# V1_1_20231208_1.net
KiCad netlist of a schematic drawn in Altium Designer
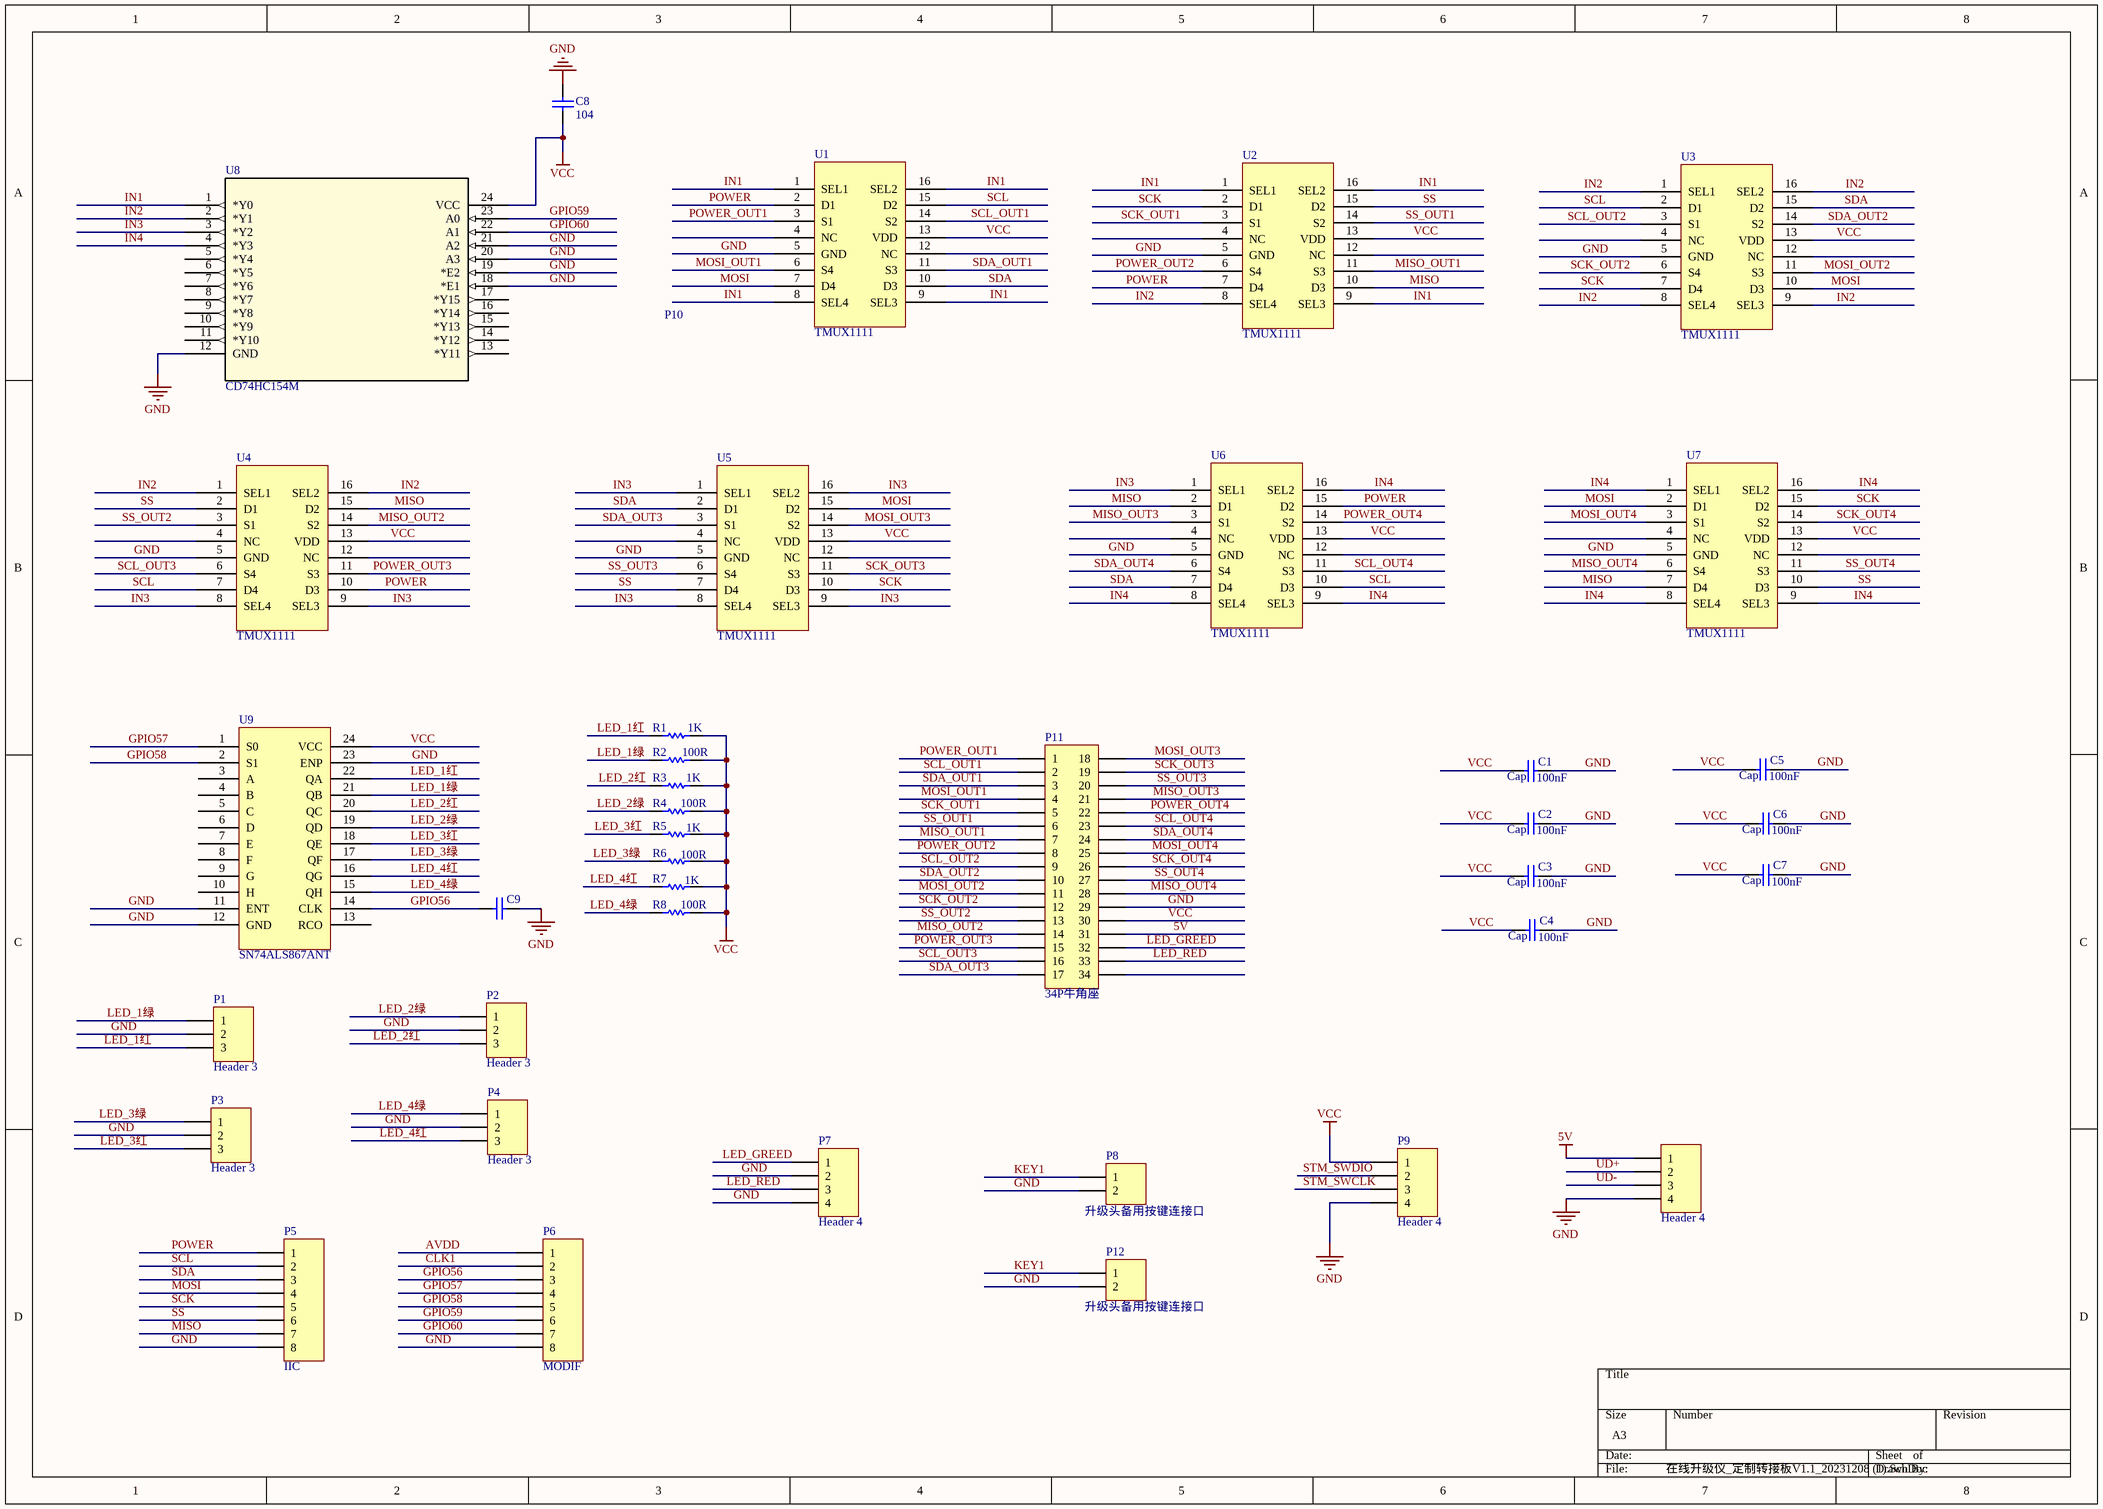
[diagram p0: 在线升级仪_定制转接板V1.1_20231208 (1).SchDoc]

(export (version "E")
  (design (tool "Eeschema 10.0.6"))
  (components
    (comp (ref "C1")
      (value "Cap")
      (footprint "0603")
      (description "Capacitor")
      (fields (field (name "ALTIUM_VALUE") "100nF") (field (name "PUBLISHER") "Altium Limited"))
      (libsource (lib "Miscellaneous Devices") (part "Cap"))
    )
    (comp (ref "C2")
      (value "Cap")
      (footprint "0603")
      (description "Capacitor")
      (fields (field (name "ALTIUM_VALUE") "100nF") (field (name "PUBLISHER") "Altium Limited"))
      (libsource (lib "Miscellaneous Devices") (part "Cap"))
    )
    (comp (ref "C3")
      (value "Cap")
      (footprint "0603")
      (description "Capacitor")
      (fields (field (name "ALTIUM_VALUE") "100nF") (field (name "PUBLISHER") "Altium Limited"))
      (libsource (lib "Miscellaneous Devices") (part "Cap"))
    )
    (comp (ref "C4")
      (value "Cap")
      (footprint "0603")
      (description "Capacitor")
      (fields (field (name "ALTIUM_VALUE") "100nF") (field (name "PUBLISHER") "Altium Limited"))
      (libsource (lib "Miscellaneous Devices") (part "Cap"))
    )
    (comp (ref "C5")
      (value "Cap")
      (footprint "0603")
      (description "Capacitor")
      (fields (field (name "ALTIUM_VALUE") "100nF") (field (name "PUBLISHER") "Altium Limited"))
      (libsource (lib "Miscellaneous Devices") (part "Cap"))
    )
    (comp (ref "C6")
      (value "Cap")
      (footprint "0603")
      (description "Capacitor")
      (fields (field (name "ALTIUM_VALUE") "100nF") (field (name "PUBLISHER") "Altium Limited"))
      (libsource (lib "Miscellaneous Devices") (part "Cap"))
    )
    (comp (ref "C7")
      (value "Cap")
      (footprint "0603")
      (description "Capacitor")
      (fields (field (name "ALTIUM_VALUE") "100nF") (field (name "PUBLISHER") "Altium Limited"))
      (libsource (lib "Miscellaneous Devices") (part "Cap"))
    )
    (comp (ref "C8")
      (value "104")
      (footprint "0603")
      (description "Capacitor (Semiconductor SIM Model)")
      (fields (field (name "Comment") "Cap Semi") (field (name "PUBLISHER") "Altium Limited"))
      (libsource (lib "Miscellaneous Devices") (part "Cap Semi"))
    )
    (comp (ref "C9")
      (value "Cap Semi")
      (footprint "0603")
      (description "Capacitor (Semiconductor SIM Model)")
      (fields (field (name "PUBLISHER") "Altium Limited"))
      (libsource (lib "Miscellaneous Devices") (part "Cap Semi"))
    )
    (comp (ref "P1")
      (value "Header 3")
      (footprint "HDR1X3")
      (description "Header, 3-Pin")
      (fields (field (name "PUBLISHER") "Altium Limited"))
      (libsource (lib "Miscellaneous Connectors") (part "Header 3"))
    )
    (comp (ref "P2")
      (value "Header 3")
      (footprint "HDR1X3")
      (description "Header, 3-Pin")
      (fields (field (name "PUBLISHER") "Altium Limited"))
      (libsource (lib "Miscellaneous Connectors") (part "Header 3"))
    )
    (comp (ref "P3")
      (value "Header 3")
      (footprint "HDR1X3")
      (description "Header, 3-Pin")
      (fields (field (name "PUBLISHER") "Altium Limited"))
      (libsource (lib "Miscellaneous Connectors") (part "Header 3"))
    )
    (comp (ref "P4")
      (value "Header 3")
      (footprint "HDR1X3")
      (description "Header, 3-Pin")
      (fields (field (name "PUBLISHER") "Altium Limited"))
      (libsource (lib "Miscellaneous Connectors") (part "Header 3"))
    )
    (comp (ref "P5")
      (value "IIC")
      (footprint "RJ45网络插座")
      (description "Header, 8-Pin")
      (fields (field (name "PUBLISHER") "Altium Limited"))
      (libsource (lib "Miscellaneous Connectors") (part "Header 8"))
    )
    (comp (ref "P6")
      (value "MODIF")
      (footprint "RJ45网络插座")
      (description "Header, 8-Pin")
      (fields (field (name "PUBLISHER") "Altium Limited"))
      (libsource (lib "Miscellaneous Connectors") (part "Header 8"))
    )
    (comp (ref "P7")
      (value "Header 4")
      (footprint "4pin_1.25mm")
      (description "Header, 4-Pin")
      (fields (field (name "PUBLISHER") "Altium Limited"))
      (libsource (lib "Miscellaneous Connectors") (part "Header 4"))
    )
    (comp (ref "P8")
      (value "升级头备用按键连接口")
      (footprint "2P座子")
      (description "Header, 2-Pin")
      (fields (field (name "PUBLISHER") "Altium Limited"))
      (libsource (lib "Miscellaneous Connectors") (part "Header 2"))
    )
    (comp (ref "P9")
      (value "Header 4")
      (footprint "PcbLib1:4P座子")
      (description "Header, 4-Pin")
      (fields (field (name "PUBLISHER") "Altium Limited"))
      (libsource (lib "Miscellaneous Connectors") (part "Header 4"))
    )
    (comp (ref "P10")
      (value "Header 4")
      (footprint "4P座子")
      (description "Header, 4-Pin")
      (fields (field (name "PUBLISHER") "Altium Limited"))
      (libsource (lib "Miscellaneous Connectors") (part "Header 4"))
    )
    (comp (ref "P11")
      (value "34P牛角座")
      (footprint "34P 牛角座")
      (description "Header, 17-Pin, Dual row")
      (fields (field (name "PUBLISHER") "Altium Limited"))
      (libsource (lib "Miscellaneous Connectors") (part "Header 17X2A"))
    )
    (comp (ref "P12")
      (value "升级头备用按键连接口")
      (footprint "2P座子")
      (description "Header, 2-Pin")
      (fields (field (name "PUBLISHER") "Altium Limited"))
      (libsource (lib "Miscellaneous Connectors") (part "Header 2"))
    )
    (comp (ref "R1")
      (value "1K")
      (footprint "0603")
      (description "Resistor")
      (fields (field (name "Comment") "Res1") (field (name "PUBLISHER") "Altium Limited"))
      (libsource (lib "Miscellaneous Devices") (part "Res1"))
    )
    (comp (ref "R2")
      (value "100R")
      (footprint "0603")
      (description "Resistor")
      (fields (field (name "Comment") "Res1") (field (name "PUBLISHER") "Altium Limited"))
      (libsource (lib "Miscellaneous Devices") (part "Res1"))
    )
    (comp (ref "R3")
      (value "1K")
      (footprint "0603")
      (description "Resistor")
      (fields (field (name "Comment") "Res1") (field (name "PUBLISHER") "Altium Limited"))
      (libsource (lib "Miscellaneous Devices") (part "Res1"))
    )
    (comp (ref "R4")
      (value "100R")
      (footprint "0603")
      (description "Resistor")
      (fields (field (name "Comment") "Res1") (field (name "PUBLISHER") "Altium Limited"))
      (libsource (lib "Miscellaneous Devices") (part "Res1"))
    )
    (comp (ref "R5")
      (value "1K")
      (footprint "0603")
      (description "Resistor")
      (fields (field (name "Comment") "Res1") (field (name "PUBLISHER") "Altium Limited"))
      (libsource (lib "Miscellaneous Devices") (part "Res1"))
    )
    (comp (ref "R6")
      (value "100R")
      (footprint "0603")
      (description "Resistor")
      (fields (field (name "Comment") "Res1") (field (name "PUBLISHER") "Altium Limited"))
      (libsource (lib "Miscellaneous Devices") (part "Res1"))
    )
    (comp (ref "R7")
      (value "1K")
      (footprint "0603")
      (description "Resistor")
      (fields (field (name "Comment") "Res1") (field (name "PUBLISHER") "Altium Limited"))
      (libsource (lib "Miscellaneous Devices") (part "Res1"))
    )
    (comp (ref "R8")
      (value "100R")
      (footprint "0603")
      (description "Resistor")
      (fields (field (name "Comment") "Res1") (field (name "PUBLISHER") "Altium Limited"))
      (libsource (lib "Miscellaneous Devices") (part "Res1"))
    )
    (comp (ref "U1")
      (value "TMUX1111")
      (footprint "TMUX1111")
      (libsource (lib "Schlib1") (part "Component_3"))
    )
    (comp (ref "U2")
      (value "TMUX1111")
      (footprint "TMUX1111")
      (libsource (lib "Schlib1") (part "Component_3"))
    )
    (comp (ref "U3")
      (value "TMUX1111")
      (footprint "TMUX1111")
      (libsource (lib "Schlib1") (part "Component_3"))
    )
    (comp (ref "U4")
      (value "TMUX1111")
      (footprint "TMUX1111")
      (libsource (lib "Schlib1") (part "Component_3"))
    )
    (comp (ref "U5")
      (value "TMUX1111")
      (footprint "TMUX1111")
      (libsource (lib "Schlib1") (part "Component_3"))
    )
    (comp (ref "U6")
      (value "TMUX1111")
      (footprint "TMUX1111")
      (libsource (lib "Schlib1") (part "Component_3"))
    )
    (comp (ref "U7")
      (value "TMUX1111")
      (footprint "TMUX1111")
      (libsource (lib "Schlib1") (part "Component_3"))
    )
    (comp (ref "U8")
      (value "CD74HC154M")
      (footprint "CD74HC154M")
      (description "High Speed CMOS Logic 4-to-16 Line Decoder/Demultiplexer")
      (fields
        (field (name "MANUFACTURER") "Texas Instruments")
        (field (name "GENERIC_PART_NUMBER") "CD74HC154")
        (field (name "COPYRIGHT") "Copyright (C) 2018 Accelerated Designs. All rights reserved")
      )
      (libsource (lib "*") (part "CD74HC154M"))
    )
    (comp (ref "U9")
      (value "SN74ALS867ANT")
      (footprint "SN74ALS867ANT")
      (libsource (lib "Schlib1") (part "Component_2"))
    )
  )
  (nets
    (net (code "1") (name "/AVDD") (class "Default")
      (node (ref "P6") (pin "1") (pinfunction "1_1") (pintype "passive"))
    )
    (net (code "2") (name "/CLK1") (class "Default")
      (node (ref "P6") (pin "2") (pinfunction "2_2") (pintype "passive"))
    )
    (net (code "3") (name "/GPIO56") (class "Default")
      (node (ref "C9") (pin "2") (pinfunction "2_2") (pintype "passive"))
      (node (ref "P6") (pin "3") (pinfunction "3_3") (pintype "passive"))
      (node (ref "U9") (pin "14") (pinfunction "CLK_14") (pintype "passive"))
    )
    (net (code "4") (name "/GPIO57") (class "Default")
      (node (ref "P6") (pin "4") (pinfunction "4_4") (pintype "passive"))
      (node (ref "U9") (pin "1") (pinfunction "S0_1") (pintype "passive"))
    )
    (net (code "5") (name "/GPIO58") (class "Default")
      (node (ref "P6") (pin "5") (pinfunction "5_5") (pintype "passive"))
      (node (ref "U9") (pin "2") (pinfunction "S1_2") (pintype "passive"))
    )
    (net (code "6") (name "/GPIO59") (class "Default")
      (node (ref "P6") (pin "6") (pinfunction "6_6") (pintype "passive"))
      (node (ref "U8") (pin "23") (pinfunction "A0_23") (pintype "input"))
    )
    (net (code "7") (name "/GPIO60") (class "Default")
      (node (ref "P6") (pin "7") (pinfunction "7_7") (pintype "passive"))
      (node (ref "U8") (pin "22") (pinfunction "A1_22") (pintype "input"))
    )
    (net (code "8") (name "/IN1") (class "Default")
      (node (ref "U1") (pin "1") (pinfunction "SEL1_1") (pintype "passive"))
      (node (ref "U1") (pin "16") (pinfunction "SEL2_16") (pintype "passive"))
      (node (ref "U1") (pin "8") (pinfunction "SEL4_8") (pintype "passive"))
      (node (ref "U1") (pin "9") (pinfunction "SEL3_9") (pintype "passive"))
      (node (ref "U2") (pin "1") (pinfunction "SEL1_1") (pintype "passive"))
      (node (ref "U2") (pin "16") (pinfunction "SEL2_16") (pintype "passive"))
      (node (ref "U2") (pin "9") (pinfunction "SEL3_9") (pintype "passive"))
      (node (ref "U8") (pin "1") (pinfunction "*Y0_1") (pintype "output"))
    )
    (net (code "9") (name "/IN2") (class "Default")
      (node (ref "U2") (pin "8") (pinfunction "SEL4_8") (pintype "passive"))
      (node (ref "U3") (pin "1") (pinfunction "SEL1_1") (pintype "passive"))
      (node (ref "U3") (pin "16") (pinfunction "SEL2_16") (pintype "passive"))
      (node (ref "U3") (pin "8") (pinfunction "SEL4_8") (pintype "passive"))
      (node (ref "U3") (pin "9") (pinfunction "SEL3_9") (pintype "passive"))
      (node (ref "U4") (pin "1") (pinfunction "SEL1_1") (pintype "passive"))
      (node (ref "U4") (pin "16") (pinfunction "SEL2_16") (pintype "passive"))
      (node (ref "U8") (pin "2") (pinfunction "*Y1_2") (pintype "output"))
    )
    (net (code "10") (name "/IN3") (class "Default")
      (node (ref "U4") (pin "8") (pinfunction "SEL4_8") (pintype "passive"))
      (node (ref "U4") (pin "9") (pinfunction "SEL3_9") (pintype "passive"))
      (node (ref "U5") (pin "1") (pinfunction "SEL1_1") (pintype "passive"))
      (node (ref "U5") (pin "16") (pinfunction "SEL2_16") (pintype "passive"))
      (node (ref "U5") (pin "8") (pinfunction "SEL4_8") (pintype "passive"))
      (node (ref "U5") (pin "9") (pinfunction "SEL3_9") (pintype "passive"))
      (node (ref "U6") (pin "1") (pinfunction "SEL1_1") (pintype "passive"))
      (node (ref "U8") (pin "3") (pinfunction "*Y2_3") (pintype "output"))
    )
    (net (code "11") (name "/IN4") (class "Default")
      (node (ref "U6") (pin "16") (pinfunction "SEL2_16") (pintype "passive"))
      (node (ref "U6") (pin "8") (pinfunction "SEL4_8") (pintype "passive"))
      (node (ref "U6") (pin "9") (pinfunction "SEL3_9") (pintype "passive"))
      (node (ref "U7") (pin "1") (pinfunction "SEL1_1") (pintype "passive"))
      (node (ref "U7") (pin "16") (pinfunction "SEL2_16") (pintype "passive"))
      (node (ref "U7") (pin "8") (pinfunction "SEL4_8") (pintype "passive"))
      (node (ref "U7") (pin "9") (pinfunction "SEL3_9") (pintype "passive"))
      (node (ref "U8") (pin "4") (pinfunction "*Y3_4") (pintype "output"))
    )
    (net (code "12") (name "/KEY1") (class "Default")
      (node (ref "P12") (pin "1") (pinfunction "1_1") (pintype "passive"))
      (node (ref "P8") (pin "1") (pinfunction "1_1") (pintype "passive"))
    )
    (net (code "13") (name "/LED_1红") (class "Default")
      (node (ref "P1") (pin "3") (pinfunction "3_3") (pintype "passive"))
      (node (ref "R1") (pin "2") (pinfunction "2_2") (pintype "passive"))
      (node (ref "U9") (pin "22") (pinfunction "QA_22") (pintype "passive"))
    )
    (net (code "14") (name "/LED_1绿") (class "Default")
      (node (ref "P1") (pin "1") (pinfunction "1_1") (pintype "passive"))
      (node (ref "R2") (pin "2") (pinfunction "2_2") (pintype "passive"))
      (node (ref "U9") (pin "21") (pinfunction "QB_21") (pintype "passive"))
    )
    (net (code "15") (name "/LED_2红") (class "Default")
      (node (ref "P2") (pin "3") (pinfunction "3_3") (pintype "passive"))
      (node (ref "R3") (pin "2") (pinfunction "2_2") (pintype "passive"))
      (node (ref "U9") (pin "20") (pinfunction "QC_20") (pintype "passive"))
    )
    (net (code "16") (name "/LED_2绿") (class "Default")
      (node (ref "P2") (pin "1") (pinfunction "1_1") (pintype "passive"))
      (node (ref "R4") (pin "2") (pinfunction "2_2") (pintype "passive"))
      (node (ref "U9") (pin "19") (pinfunction "QD_19") (pintype "passive"))
    )
    (net (code "17") (name "/LED_3红") (class "Default")
      (node (ref "P3") (pin "3") (pinfunction "3_3") (pintype "passive"))
      (node (ref "R5") (pin "2") (pinfunction "2_2") (pintype "passive"))
      (node (ref "U9") (pin "18") (pinfunction "QE_18") (pintype "passive"))
    )
    (net (code "18") (name "/LED_3绿") (class "Default")
      (node (ref "P3") (pin "1") (pinfunction "1_1") (pintype "passive"))
      (node (ref "R6") (pin "2") (pinfunction "2_2") (pintype "passive"))
      (node (ref "U9") (pin "17") (pinfunction "QF_17") (pintype "passive"))
    )
    (net (code "19") (name "/LED_4红") (class "Default")
      (node (ref "P4") (pin "3") (pinfunction "3_3") (pintype "passive"))
      (node (ref "R7") (pin "2") (pinfunction "2_2") (pintype "passive"))
      (node (ref "U9") (pin "16") (pinfunction "QG_16") (pintype "passive"))
    )
    (net (code "20") (name "/LED_4绿") (class "Default")
      (node (ref "P4") (pin "1") (pinfunction "1_1") (pintype "passive"))
      (node (ref "R8") (pin "2") (pinfunction "2_2") (pintype "passive"))
      (node (ref "U9") (pin "15") (pinfunction "QH_15") (pintype "passive"))
    )
    (net (code "21") (name "/LED_GREED") (class "Default")
      (node (ref "P11") (pin "32") (pinfunction "32_32") (pintype "passive"))
      (node (ref "P7") (pin "1") (pinfunction "1_1") (pintype "passive"))
    )
    (net (code "22") (name "/LED_RED") (class "Default")
      (node (ref "P11") (pin "33") (pinfunction "33_33") (pintype "passive"))
      (node (ref "P7") (pin "3") (pinfunction "3_3") (pintype "passive"))
    )
    (net (code "23") (name "/MISO") (class "Default")
      (node (ref "P5") (pin "7") (pinfunction "7_7") (pintype "passive"))
      (node (ref "U2") (pin "10") (pinfunction "D3_10") (pintype "passive"))
      (node (ref "U4") (pin "15") (pinfunction "D2_15") (pintype "passive"))
      (node (ref "U6") (pin "2") (pinfunction "D1_2") (pintype "passive"))
      (node (ref "U7") (pin "7") (pinfunction "D4_7") (pintype "passive"))
    )
    (net (code "24") (name "/MISO_OUT1") (class "Default")
      (node (ref "P11") (pin "7") (pinfunction "7_7") (pintype "passive"))
      (node (ref "U2") (pin "11") (pinfunction "S3_11") (pintype "passive"))
    )
    (net (code "25") (name "/MISO_OUT2") (class "Default")
      (node (ref "P11") (pin "14") (pinfunction "14_14") (pintype "passive"))
      (node (ref "U4") (pin "14") (pinfunction "S2_14") (pintype "passive"))
    )
    (net (code "26") (name "/MISO_OUT3") (class "Default")
      (node (ref "P11") (pin "21") (pinfunction "21_21") (pintype "passive"))
      (node (ref "U6") (pin "3") (pinfunction "S1_3") (pintype "passive"))
    )
    (net (code "27") (name "/MISO_OUT4") (class "Default")
      (node (ref "P11") (pin "28") (pinfunction "28_28") (pintype "passive"))
      (node (ref "U7") (pin "6") (pinfunction "S4_6") (pintype "passive"))
    )
    (net (code "28") (name "/MOSI") (class "Default")
      (node (ref "P5") (pin "4") (pinfunction "4_4") (pintype "passive"))
      (node (ref "U1") (pin "7") (pinfunction "D4_7") (pintype "passive"))
      (node (ref "U3") (pin "10") (pinfunction "D3_10") (pintype "passive"))
      (node (ref "U5") (pin "15") (pinfunction "D2_15") (pintype "passive"))
      (node (ref "U7") (pin "2") (pinfunction "D1_2") (pintype "passive"))
    )
    (net (code "29") (name "/MOSI_OUT1") (class "Default")
      (node (ref "P11") (pin "4") (pinfunction "4_4") (pintype "passive"))
      (node (ref "U1") (pin "6") (pinfunction "S4_6") (pintype "passive"))
    )
    (net (code "30") (name "/MOSI_OUT2") (class "Default")
      (node (ref "P11") (pin "11") (pinfunction "11_11") (pintype "passive"))
      (node (ref "U3") (pin "11") (pinfunction "S3_11") (pintype "passive"))
    )
    (net (code "31") (name "/MOSI_OUT3") (class "Default")
      (node (ref "P11") (pin "18") (pinfunction "18_18") (pintype "passive"))
      (node (ref "U5") (pin "14") (pinfunction "S2_14") (pintype "passive"))
    )
    (net (code "32") (name "/MOSI_OUT4") (class "Default")
      (node (ref "P11") (pin "25") (pinfunction "25_25") (pintype "passive"))
      (node (ref "U7") (pin "3") (pinfunction "S1_3") (pintype "passive"))
    )
    (net (code "33") (name "/POWER") (class "Default")
      (node (ref "P5") (pin "1") (pinfunction "1_1") (pintype "passive"))
      (node (ref "U1") (pin "2") (pinfunction "D1_2") (pintype "passive"))
      (node (ref "U2") (pin "7") (pinfunction "D4_7") (pintype "passive"))
      (node (ref "U4") (pin "10") (pinfunction "D3_10") (pintype "passive"))
      (node (ref "U6") (pin "15") (pinfunction "D2_15") (pintype "passive"))
    )
    (net (code "34") (name "/POWER_OUT1") (class "Default")
      (node (ref "P11") (pin "1") (pinfunction "1_1") (pintype "passive"))
      (node (ref "U1") (pin "3") (pinfunction "S1_3") (pintype "passive"))
    )
    (net (code "35") (name "/POWER_OUT2") (class "Default")
      (node (ref "P11") (pin "8") (pinfunction "8_8") (pintype "passive"))
      (node (ref "U2") (pin "6") (pinfunction "S4_6") (pintype "passive"))
    )
    (net (code "36") (name "/POWER_OUT3") (class "Default")
      (node (ref "P11") (pin "15") (pinfunction "15_15") (pintype "passive"))
      (node (ref "U4") (pin "11") (pinfunction "S3_11") (pintype "passive"))
    )
    (net (code "37") (name "/POWER_OUT4") (class "Default")
      (node (ref "P11") (pin "22") (pinfunction "22_22") (pintype "passive"))
      (node (ref "U6") (pin "14") (pinfunction "S2_14") (pintype "passive"))
    )
    (net (code "38") (name "/SCK") (class "Default")
      (node (ref "P5") (pin "5") (pinfunction "5_5") (pintype "passive"))
      (node (ref "U2") (pin "2") (pinfunction "D1_2") (pintype "passive"))
      (node (ref "U3") (pin "7") (pinfunction "D4_7") (pintype "passive"))
      (node (ref "U5") (pin "10") (pinfunction "D3_10") (pintype "passive"))
      (node (ref "U7") (pin "15") (pinfunction "D2_15") (pintype "passive"))
    )
    (net (code "39") (name "/SCK_OUT1") (class "Default")
      (node (ref "P11") (pin "5") (pinfunction "5_5") (pintype "passive"))
      (node (ref "U2") (pin "3") (pinfunction "S1_3") (pintype "passive"))
    )
    (net (code "40") (name "/SCK_OUT2") (class "Default")
      (node (ref "P11") (pin "12") (pinfunction "12_12") (pintype "passive"))
      (node (ref "U3") (pin "6") (pinfunction "S4_6") (pintype "passive"))
    )
    (net (code "41") (name "/SCK_OUT3") (class "Default")
      (node (ref "P11") (pin "19") (pinfunction "19_19") (pintype "passive"))
      (node (ref "U5") (pin "11") (pinfunction "S3_11") (pintype "passive"))
    )
    (net (code "42") (name "/SCK_OUT4") (class "Default")
      (node (ref "P11") (pin "26") (pinfunction "26_26") (pintype "passive"))
      (node (ref "U7") (pin "14") (pinfunction "S2_14") (pintype "passive"))
    )
    (net (code "43") (name "/SCL") (class "Default")
      (node (ref "P5") (pin "2") (pinfunction "2_2") (pintype "passive"))
      (node (ref "U1") (pin "15") (pinfunction "D2_15") (pintype "passive"))
      (node (ref "U3") (pin "2") (pinfunction "D1_2") (pintype "passive"))
      (node (ref "U4") (pin "7") (pinfunction "D4_7") (pintype "passive"))
      (node (ref "U6") (pin "10") (pinfunction "D3_10") (pintype "passive"))
    )
    (net (code "44") (name "/SCL_OUT1") (class "Default")
      (node (ref "P11") (pin "2") (pinfunction "2_2") (pintype "passive"))
      (node (ref "U1") (pin "14") (pinfunction "S2_14") (pintype "passive"))
    )
    (net (code "45") (name "/SCL_OUT2") (class "Default")
      (node (ref "P11") (pin "9") (pinfunction "9_9") (pintype "passive"))
      (node (ref "U3") (pin "3") (pinfunction "S1_3") (pintype "passive"))
    )
    (net (code "46") (name "/SCL_OUT3") (class "Default")
      (node (ref "P11") (pin "16") (pinfunction "16_16") (pintype "passive"))
      (node (ref "U4") (pin "6") (pinfunction "S4_6") (pintype "passive"))
    )
    (net (code "47") (name "/SCL_OUT4") (class "Default")
      (node (ref "P11") (pin "23") (pinfunction "23_23") (pintype "passive"))
      (node (ref "U6") (pin "11") (pinfunction "S3_11") (pintype "passive"))
    )
    (net (code "48") (name "/SDA") (class "Default")
      (node (ref "P5") (pin "3") (pinfunction "3_3") (pintype "passive"))
      (node (ref "U1") (pin "10") (pinfunction "D3_10") (pintype "passive"))
      (node (ref "U3") (pin "15") (pinfunction "D2_15") (pintype "passive"))
      (node (ref "U5") (pin "2") (pinfunction "D1_2") (pintype "passive"))
      (node (ref "U6") (pin "7") (pinfunction "D4_7") (pintype "passive"))
    )
    (net (code "49") (name "/SDA_OUT1") (class "Default")
      (node (ref "P11") (pin "3") (pinfunction "3_3") (pintype "passive"))
      (node (ref "U1") (pin "11") (pinfunction "S3_11") (pintype "passive"))
    )
    (net (code "50") (name "/SDA_OUT2") (class "Default")
      (node (ref "P11") (pin "10") (pinfunction "10_10") (pintype "passive"))
      (node (ref "U3") (pin "14") (pinfunction "S2_14") (pintype "passive"))
    )
    (net (code "51") (name "/SDA_OUT3") (class "Default")
      (node (ref "P11") (pin "17") (pinfunction "17_17") (pintype "passive"))
      (node (ref "U5") (pin "3") (pinfunction "S1_3") (pintype "passive"))
    )
    (net (code "52") (name "/SDA_OUT4") (class "Default")
      (node (ref "P11") (pin "24") (pinfunction "24_24") (pintype "passive"))
      (node (ref "U6") (pin "6") (pinfunction "S4_6") (pintype "passive"))
    )
    (net (code "53") (name "/SS") (class "Default")
      (node (ref "P5") (pin "6") (pinfunction "6_6") (pintype "passive"))
      (node (ref "U2") (pin "15") (pinfunction "D2_15") (pintype "passive"))
      (node (ref "U4") (pin "2") (pinfunction "D1_2") (pintype "passive"))
      (node (ref "U5") (pin "7") (pinfunction "D4_7") (pintype "passive"))
      (node (ref "U7") (pin "10") (pinfunction "D3_10") (pintype "passive"))
    )
    (net (code "54") (name "/SS_OUT1") (class "Default")
      (node (ref "P11") (pin "6") (pinfunction "6_6") (pintype "passive"))
      (node (ref "U2") (pin "14") (pinfunction "S2_14") (pintype "passive"))
    )
    (net (code "55") (name "/SS_OUT2") (class "Default")
      (node (ref "P11") (pin "13") (pinfunction "13_13") (pintype "passive"))
      (node (ref "U4") (pin "3") (pinfunction "S1_3") (pintype "passive"))
    )
    (net (code "56") (name "/SS_OUT3") (class "Default")
      (node (ref "P11") (pin "20") (pinfunction "20_20") (pintype "passive"))
      (node (ref "U5") (pin "6") (pinfunction "S4_6") (pintype "passive"))
    )
    (net (code "57") (name "/SS_OUT4") (class "Default")
      (node (ref "P11") (pin "27") (pinfunction "27_27") (pintype "passive"))
      (node (ref "U7") (pin "11") (pinfunction "S3_11") (pintype "passive"))
    )
    (net (code "58") (name "/STM_SWCLK") (class "Default")
      (node (ref "P9") (pin "3") (pinfunction "3_3") (pintype "passive"))
    )
    (net (code "59") (name "/STM_SWDIO") (class "Default")
      (node (ref "P9") (pin "2") (pinfunction "2_2") (pintype "passive"))
    )
    (net (code "60") (name "/UD+") (class "Default")
      (node (ref "P10") (pin "2") (pinfunction "2_2") (pintype "passive"))
    )
    (net (code "61") (name "/UD-") (class "Default")
      (node (ref "P10") (pin "3") (pinfunction "3_3") (pintype "passive"))
    )
    (net (code "62") (name "5V") (class "Default")
      (node (ref "P10") (pin "1") (pinfunction "1_1") (pintype "passive"))
      (node (ref "P11") (pin "31") (pinfunction "31_31") (pintype "passive"))
    )
    (net (code "63") (name "GND") (class "Default")
      (node (ref "C1") (pin "2") (pinfunction "2_2") (pintype "passive"))
      (node (ref "C2") (pin "2") (pinfunction "2_2") (pintype "passive"))
      (node (ref "C3") (pin "2") (pinfunction "2_2") (pintype "passive"))
      (node (ref "C4") (pin "2") (pinfunction "2_2") (pintype "passive"))
      (node (ref "C5") (pin "2") (pinfunction "2_2") (pintype "passive"))
      (node (ref "C6") (pin "2") (pinfunction "2_2") (pintype "passive"))
      (node (ref "C7") (pin "2") (pinfunction "2_2") (pintype "passive"))
      (node (ref "C8") (pin "1") (pinfunction "1_1") (pintype "passive"))
      (node (ref "C9") (pin "1") (pinfunction "1_1") (pintype "passive"))
      (node (ref "P1") (pin "2") (pinfunction "2_2") (pintype "passive"))
      (node (ref "P10") (pin "4") (pinfunction "4_4") (pintype "passive"))
      (node (ref "P11") (pin "29") (pinfunction "29_29") (pintype "passive"))
      (node (ref "P12") (pin "2") (pinfunction "2_2") (pintype "passive"))
      (node (ref "P2") (pin "2") (pinfunction "2_2") (pintype "passive"))
      (node (ref "P3") (pin "2") (pinfunction "2_2") (pintype "passive"))
      (node (ref "P4") (pin "2") (pinfunction "2_2") (pintype "passive"))
      (node (ref "P5") (pin "8") (pinfunction "8_8") (pintype "passive"))
      (node (ref "P6") (pin "8") (pinfunction "8_8") (pintype "passive"))
      (node (ref "P7") (pin "2") (pinfunction "2_2") (pintype "passive"))
      (node (ref "P7") (pin "4") (pinfunction "4_4") (pintype "passive"))
      (node (ref "P8") (pin "2") (pinfunction "2_2") (pintype "passive"))
      (node (ref "P9") (pin "4") (pinfunction "4_4") (pintype "passive"))
      (node (ref "U1") (pin "5") (pinfunction "GND_5") (pintype "passive"))
      (node (ref "U2") (pin "5") (pinfunction "GND_5") (pintype "passive"))
      (node (ref "U3") (pin "5") (pinfunction "GND_5") (pintype "passive"))
      (node (ref "U4") (pin "5") (pinfunction "GND_5") (pintype "passive"))
      (node (ref "U5") (pin "5") (pinfunction "GND_5") (pintype "passive"))
      (node (ref "U6") (pin "5") (pinfunction "GND_5") (pintype "passive"))
      (node (ref "U7") (pin "5") (pinfunction "GND_5") (pintype "passive"))
      (node (ref "U8") (pin "12") (pinfunction "GND_12") (pintype "power_in"))
      (node (ref "U8") (pin "18") (pinfunction "*E1_18") (pintype "input"))
      (node (ref "U8") (pin "19") (pinfunction "*E2_19") (pintype "input"))
      (node (ref "U8") (pin "20") (pinfunction "A3_20") (pintype "input"))
      (node (ref "U8") (pin "21") (pinfunction "A2_21") (pintype "input"))
      (node (ref "U9") (pin "11") (pinfunction "ENT_11") (pintype "passive"))
      (node (ref "U9") (pin "12") (pinfunction "GND_12") (pintype "passive"))
      (node (ref "U9") (pin "23") (pinfunction "ENP_23") (pintype "passive"))
    )
    (net (code "64") (name "VCC") (class "Default")
      (node (ref "C1") (pin "1") (pinfunction "1_1") (pintype "passive"))
      (node (ref "C2") (pin "1") (pinfunction "1_1") (pintype "passive"))
      (node (ref "C3") (pin "1") (pinfunction "1_1") (pintype "passive"))
      (node (ref "C4") (pin "1") (pinfunction "1_1") (pintype "passive"))
      (node (ref "C5") (pin "1") (pinfunction "1_1") (pintype "passive"))
      (node (ref "C6") (pin "1") (pinfunction "1_1") (pintype "passive"))
      (node (ref "C7") (pin "1") (pinfunction "1_1") (pintype "passive"))
      (node (ref "C8") (pin "2") (pinfunction "2_2") (pintype "passive"))
      (node (ref "P11") (pin "30") (pinfunction "30_30") (pintype "passive"))
      (node (ref "P9") (pin "1") (pinfunction "1_1") (pintype "passive"))
      (node (ref "R1") (pin "1") (pinfunction "1_1") (pintype "passive"))
      (node (ref "R2") (pin "1") (pinfunction "1_1") (pintype "passive"))
      (node (ref "R3") (pin "1") (pinfunction "1_1") (pintype "passive"))
      (node (ref "R4") (pin "1") (pinfunction "1_1") (pintype "passive"))
      (node (ref "R5") (pin "1") (pinfunction "1_1") (pintype "passive"))
      (node (ref "R6") (pin "1") (pinfunction "1_1") (pintype "passive"))
      (node (ref "R7") (pin "1") (pinfunction "1_1") (pintype "passive"))
      (node (ref "R8") (pin "1") (pinfunction "1_1") (pintype "passive"))
      (node (ref "U1") (pin "13") (pinfunction "VDD_13") (pintype "passive"))
      (node (ref "U2") (pin "13") (pinfunction "VDD_13") (pintype "passive"))
      (node (ref "U3") (pin "13") (pinfunction "VDD_13") (pintype "passive"))
      (node (ref "U4") (pin "13") (pinfunction "VDD_13") (pintype "passive"))
      (node (ref "U5") (pin "13") (pinfunction "VDD_13") (pintype "passive"))
      (node (ref "U6") (pin "13") (pinfunction "VDD_13") (pintype "passive"))
      (node (ref "U7") (pin "13") (pinfunction "VDD_13") (pintype "passive"))
      (node (ref "U8") (pin "24") (pinfunction "VCC_24") (pintype "power_in"))
      (node (ref "U9") (pin "24") (pinfunction "VCC_24") (pintype "passive"))
    )
    (net (code "65") (name "unconnected-(P11-Pad34)") (class "Default")
      (node (ref "P11") (pin "34") (pinfunction "34_34") (pintype "passive"))
    )
    (net (code "66") (name "unconnected-(U1-NC-Pad4)") (class "Default")
      (node (ref "U1") (pin "4") (pinfunction "NC_4") (pintype "passive"))
    )
    (net (code "67") (name "unconnected-(U1-NC-Pad12)") (class "Default")
      (node (ref "U1") (pin "12") (pinfunction "NC_12") (pintype "passive"))
    )
    (net (code "68") (name "unconnected-(U2-NC-Pad4)") (class "Default")
      (node (ref "U2") (pin "4") (pinfunction "NC_4") (pintype "passive"))
    )
    (net (code "69") (name "unconnected-(U2-NC-Pad12)") (class "Default")
      (node (ref "U2") (pin "12") (pinfunction "NC_12") (pintype "passive"))
    )
    (net (code "70") (name "unconnected-(U3-NC-Pad4)") (class "Default")
      (node (ref "U3") (pin "4") (pinfunction "NC_4") (pintype "passive"))
    )
    (net (code "71") (name "unconnected-(U3-NC-Pad12)") (class "Default")
      (node (ref "U3") (pin "12") (pinfunction "NC_12") (pintype "passive"))
    )
    (net (code "72") (name "unconnected-(U4-NC-Pad4)") (class "Default")
      (node (ref "U4") (pin "4") (pinfunction "NC_4") (pintype "passive"))
    )
    (net (code "73") (name "unconnected-(U4-NC-Pad12)") (class "Default")
      (node (ref "U4") (pin "12") (pinfunction "NC_12") (pintype "passive"))
    )
    (net (code "74") (name "unconnected-(U5-NC-Pad4)") (class "Default")
      (node (ref "U5") (pin "4") (pinfunction "NC_4") (pintype "passive"))
    )
    (net (code "75") (name "unconnected-(U5-NC-Pad12)") (class "Default")
      (node (ref "U5") (pin "12") (pinfunction "NC_12") (pintype "passive"))
    )
    (net (code "76") (name "unconnected-(U6-NC-Pad4)") (class "Default")
      (node (ref "U6") (pin "4") (pinfunction "NC_4") (pintype "passive"))
    )
    (net (code "77") (name "unconnected-(U6-NC-Pad12)") (class "Default")
      (node (ref "U6") (pin "12") (pinfunction "NC_12") (pintype "passive"))
    )
    (net (code "78") (name "unconnected-(U7-NC-Pad4)") (class "Default")
      (node (ref "U7") (pin "4") (pinfunction "NC_4") (pintype "passive"))
    )
    (net (code "79") (name "unconnected-(U7-NC-Pad12)") (class "Default")
      (node (ref "U7") (pin "12") (pinfunction "NC_12") (pintype "passive"))
    )
    (net (code "80") (name "unconnected-(U8-*Y4-Pad5)") (class "Default")
      (node (ref "U8") (pin "5") (pinfunction "*Y4_5") (pintype "output"))
    )
    (net (code "81") (name "unconnected-(U8-*Y5-Pad6)") (class "Default")
      (node (ref "U8") (pin "6") (pinfunction "*Y5_6") (pintype "output"))
    )
    (net (code "82") (name "unconnected-(U8-*Y6-Pad7)") (class "Default")
      (node (ref "U8") (pin "7") (pinfunction "*Y6_7") (pintype "output"))
    )
    (net (code "83") (name "unconnected-(U8-*Y7-Pad8)") (class "Default")
      (node (ref "U8") (pin "8") (pinfunction "*Y7_8") (pintype "output"))
    )
    (net (code "84") (name "unconnected-(U8-*Y8-Pad9)") (class "Default")
      (node (ref "U8") (pin "9") (pinfunction "*Y8_9") (pintype "output"))
    )
    (net (code "85") (name "unconnected-(U8-*Y9-Pad10)") (class "Default")
      (node (ref "U8") (pin "10") (pinfunction "*Y9_10") (pintype "output"))
    )
    (net (code "86") (name "unconnected-(U8-*Y10-Pad11)") (class "Default")
      (node (ref "U8") (pin "11") (pinfunction "*Y10_11") (pintype "output"))
    )
    (net (code "87") (name "unconnected-(U8-*Y11-Pad13)") (class "Default")
      (node (ref "U8") (pin "13") (pinfunction "*Y11_13") (pintype "output"))
    )
    (net (code "88") (name "unconnected-(U8-*Y12-Pad14)") (class "Default")
      (node (ref "U8") (pin "14") (pinfunction "*Y12_14") (pintype "output"))
    )
    (net (code "89") (name "unconnected-(U8-*Y13-Pad15)") (class "Default")
      (node (ref "U8") (pin "15") (pinfunction "*Y13_15") (pintype "output"))
    )
    (net (code "90") (name "unconnected-(U8-*Y14-Pad16)") (class "Default")
      (node (ref "U8") (pin "16") (pinfunction "*Y14_16") (pintype "output"))
    )
    (net (code "91") (name "unconnected-(U8-*Y15-Pad17)") (class "Default")
      (node (ref "U8") (pin "17") (pinfunction "*Y15_17") (pintype "output"))
    )
    (net (code "92") (name "unconnected-(U9-A-Pad3)") (class "Default")
      (node (ref "U9") (pin "3") (pinfunction "A_3") (pintype "passive"))
    )
    (net (code "93") (name "unconnected-(U9-B-Pad4)") (class "Default")
      (node (ref "U9") (pin "4") (pinfunction "B_4") (pintype "passive"))
    )
    (net (code "94") (name "unconnected-(U9-C-Pad5)") (class "Default")
      (node (ref "U9") (pin "5") (pinfunction "C_5") (pintype "passive"))
    )
    (net (code "95") (name "unconnected-(U9-D-Pad6)") (class "Default")
      (node (ref "U9") (pin "6") (pinfunction "D_6") (pintype "passive"))
    )
    (net (code "96") (name "unconnected-(U9-E-Pad7)") (class "Default")
      (node (ref "U9") (pin "7") (pinfunction "E_7") (pintype "passive"))
    )
    (net (code "97") (name "unconnected-(U9-F-Pad8)") (class "Default")
      (node (ref "U9") (pin "8") (pinfunction "F_8") (pintype "passive"))
    )
    (net (code "98") (name "unconnected-(U9-G-Pad9)") (class "Default")
      (node (ref "U9") (pin "9") (pinfunction "G_9") (pintype "passive"))
    )
    (net (code "99") (name "unconnected-(U9-H-Pad10)") (class "Default")
      (node (ref "U9") (pin "10") (pinfunction "H_10") (pintype "passive"))
    )
    (net (code "100") (name "unconnected-(U9-RCO-Pad13)") (class "Default")
      (node (ref "U9") (pin "13") (pinfunction "RCO_13") (pintype "passive"))
    )
  )
)
